# mainboard_motor_v1_0.net
KiCad netlist of a schematic drawn in Altium Designer
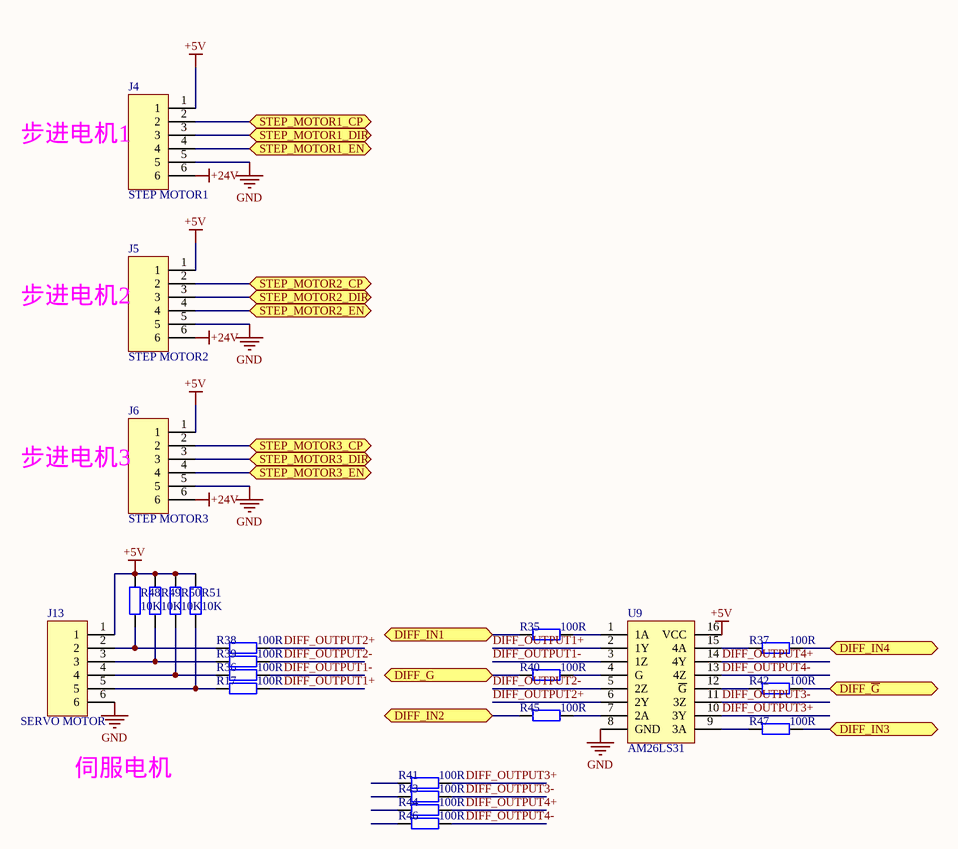
[diagram p0: mainboard_motor.v1.0.SchDoc]

(export (version "E")
  (design (tool "Eeschema 10.0.6"))
  (components
    (comp (ref "J4")
      (value "STEP MOTOR1")
      (footprint "XH2.54-6T")
      (libsource (lib "Connector") (part "SH-6"))
    )
    (comp (ref "J5")
      (value "STEP MOTOR2")
      (footprint "XH2.54-6T")
      (libsource (lib "Connector") (part "SH-6"))
    )
    (comp (ref "J6")
      (value "STEP MOTOR3")
      (footprint "XH2.54-6T")
      (libsource (lib "Connector") (part "SH-6"))
    )
    (comp (ref "J13")
      (value "SERVO MOTOR")
      (footprint "XH2.54-6T")
      (libsource (lib "Connector") (part "SH-6"))
    )
    (comp (ref "R17")
      (value "100R")
      (footprint "0805")
      (description "Resistor")
      (fields (field (name "PUBLISHER") "Altium Limited"))
      (libsource (lib "") (part "Res2_1"))
    )
    (comp (ref "R35")
      (value "100R")
      (footprint "0805")
      (description "Resistor")
      (fields (field (name "PUBLISHER") "Altium Limited"))
      (libsource (lib "") (part "Res2_1"))
    )
    (comp (ref "R36")
      (value "100R")
      (footprint "0805")
      (description "Resistor")
      (fields (field (name "PUBLISHER") "Altium Limited"))
      (libsource (lib "") (part "Res2_1"))
    )
    (comp (ref "R37")
      (value "100R")
      (footprint "0805")
      (description "Resistor")
      (fields (field (name "PUBLISHER") "Altium Limited"))
      (libsource (lib "") (part "Res2_1"))
    )
    (comp (ref "R38")
      (value "100R")
      (footprint "0805")
      (description "Resistor")
      (fields (field (name "PUBLISHER") "Altium Limited"))
      (libsource (lib "") (part "Res2_1"))
    )
    (comp (ref "R39")
      (value "100R")
      (footprint "0805")
      (description "Resistor")
      (fields (field (name "PUBLISHER") "Altium Limited"))
      (libsource (lib "") (part "Res2_1"))
    )
    (comp (ref "R40")
      (value "100R")
      (footprint "0805")
      (description "Resistor")
      (fields (field (name "PUBLISHER") "Altium Limited"))
      (libsource (lib "") (part "Res2_1"))
    )
    (comp (ref "R41")
      (value "100R")
      (footprint "0805")
      (description "Resistor")
      (fields (field (name "PUBLISHER") "Altium Limited"))
      (libsource (lib "") (part "Res2_1"))
    )
    (comp (ref "R42")
      (value "100R")
      (footprint "0805")
      (description "Resistor")
      (fields (field (name "PUBLISHER") "Altium Limited"))
      (libsource (lib "") (part "Res2_1"))
    )
    (comp (ref "R43")
      (value "100R")
      (footprint "0805")
      (description "Resistor")
      (fields (field (name "PUBLISHER") "Altium Limited"))
      (libsource (lib "") (part "Res2_1"))
    )
    (comp (ref "R44")
      (value "100R")
      (footprint "0805")
      (description "Resistor")
      (fields (field (name "PUBLISHER") "Altium Limited"))
      (libsource (lib "") (part "Res2_1"))
    )
    (comp (ref "R45")
      (value "100R")
      (footprint "0805")
      (description "Resistor")
      (fields (field (name "PUBLISHER") "Altium Limited"))
      (libsource (lib "") (part "Res2_1"))
    )
    (comp (ref "R46")
      (value "100R")
      (footprint "0805")
      (description "Resistor")
      (fields (field (name "PUBLISHER") "Altium Limited"))
      (libsource (lib "") (part "Res2_1"))
    )
    (comp (ref "R47")
      (value "100R")
      (footprint "0805")
      (description "Resistor")
      (fields (field (name "PUBLISHER") "Altium Limited"))
      (libsource (lib "") (part "Res2_1"))
    )
    (comp (ref "R48")
      (value "10K")
      (footprint "0805")
      (description "Resistor")
      (fields (field (name "PUBLISHER") "Altium Limited"))
      (libsource (lib "TIAN's Schlib") (part "Res2"))
    )
    (comp (ref "R49")
      (value "10K")
      (footprint "0805")
      (description "Resistor")
      (fields (field (name "PUBLISHER") "Altium Limited"))
      (libsource (lib "TIAN's Schlib") (part "Res2"))
    )
    (comp (ref "R50")
      (value "10K")
      (footprint "0805")
      (description "Resistor")
      (fields (field (name "PUBLISHER") "Altium Limited"))
      (libsource (lib "TIAN's Schlib") (part "Res2"))
    )
    (comp (ref "R51")
      (value "10K")
      (footprint "0805")
      (description "Resistor")
      (fields (field (name "PUBLISHER") "Altium Limited"))
      (libsource (lib "TIAN's Schlib") (part "Res2"))
    )
    (comp (ref "U9") (value "AM26LS31") (footprint "SO-16") (libsource (lib "Chip") (part "AM26LS31")))
  )
  (nets
    (net (code "1") (name "+5V") (class "Default")
      (node (ref "J13") (pin "1") (pinfunction "1_1") (pintype "passive"))
      (node (ref "J4") (pin "1") (pinfunction "1_1") (pintype "passive"))
      (node (ref "J5") (pin "1") (pinfunction "1_1") (pintype "passive"))
      (node (ref "J6") (pin "1") (pinfunction "1_1") (pintype "passive"))
      (node (ref "R48") (pin "1") (pinfunction "1_1") (pintype "passive"))
      (node (ref "R49") (pin "1") (pinfunction "1_1") (pintype "passive"))
      (node (ref "R50") (pin "1") (pinfunction "1_1") (pintype "passive"))
      (node (ref "R51") (pin "1") (pinfunction "1_1") (pintype "passive"))
      (node (ref "U9") (pin "16") (pinfunction "VCC_16") (pintype "passive"))
    )
    (net (code "2") (name "+24V") (class "Default")
      (node (ref "J4") (pin "6") (pinfunction "6_6") (pintype "passive"))
      (node (ref "J5") (pin "6") (pinfunction "6_6") (pintype "passive"))
      (node (ref "J6") (pin "6") (pinfunction "6_6") (pintype "passive"))
    )
    (net (code "3") (name "/DIFF_G") (class "Default")
      (node (ref "R40") (pin "2") (pinfunction "2_2") (pintype "passive"))
    )
    (net (code "4") (name "/DIFF_IN1") (class "Default")
      (node (ref "R35") (pin "2") (pinfunction "2_2") (pintype "passive"))
    )
    (net (code "5") (name "/DIFF_IN2") (class "Default")
      (node (ref "R45") (pin "2") (pinfunction "2_2") (pintype "passive"))
    )
    (net (code "6") (name "/DIFF_IN3") (class "Default")
      (node (ref "R47") (pin "1") (pinfunction "1_1") (pintype "passive"))
    )
    (net (code "7") (name "/DIFF_IN4") (class "Default")
      (node (ref "R37") (pin "1") (pinfunction "1_1") (pintype "passive"))
    )
    (net (code "8") (name "/DIFF_OUTPUT1+") (class "Default")
      (node (ref "R17") (pin "1") (pinfunction "1_1") (pintype "passive"))
      (node (ref "U9") (pin "2") (pinfunction "1Y_2") (pintype "passive"))
    )
    (net (code "9") (name "/DIFF_OUTPUT1-") (class "Default")
      (node (ref "R36") (pin "1") (pinfunction "1_1") (pintype "passive"))
      (node (ref "U9") (pin "3") (pinfunction "1Z_3") (pintype "passive"))
    )
    (net (code "10") (name "/DIFF_OUTPUT2+") (class "Default")
      (node (ref "R38") (pin "1") (pinfunction "1_1") (pintype "passive"))
      (node (ref "U9") (pin "6") (pinfunction "2Y_6") (pintype "passive"))
    )
    (net (code "11") (name "/DIFF_OUTPUT2-") (class "Default")
      (node (ref "R39") (pin "1") (pinfunction "1_1") (pintype "passive"))
      (node (ref "U9") (pin "5") (pinfunction "2Z_5") (pintype "passive"))
    )
    (net (code "12") (name "/DIFF_OUTPUT3+") (class "Default")
      (node (ref "R41") (pin "1") (pinfunction "1_1") (pintype "passive"))
      (node (ref "U9") (pin "10") (pinfunction "3Y_10") (pintype "passive"))
    )
    (net (code "13") (name "/DIFF_OUTPUT3-") (class "Default")
      (node (ref "R43") (pin "1") (pinfunction "1_1") (pintype "passive"))
      (node (ref "U9") (pin "11") (pinfunction "3Z_11") (pintype "passive"))
    )
    (net (code "14") (name "/DIFF_OUTPUT4+") (class "Default")
      (node (ref "R44") (pin "1") (pinfunction "1_1") (pintype "passive"))
      (node (ref "U9") (pin "14") (pinfunction "4Y_14") (pintype "passive"))
    )
    (net (code "15") (name "/DIFF_OUTPUT4-") (class "Default")
      (node (ref "R46") (pin "1") (pinfunction "1_1") (pintype "passive"))
      (node (ref "U9") (pin "13") (pinfunction "4Z_13") (pintype "passive"))
    )
    (net (code "16") (name "/DIFF_~{G}") (class "Default")
      (node (ref "R42") (pin "1") (pinfunction "1_1") (pintype "passive"))
    )
    (net (code "17") (name "/STEP_MOTOR1_CP") (class "Default")
      (node (ref "J4") (pin "2") (pinfunction "2_2") (pintype "passive"))
    )
    (net (code "18") (name "/STEP_MOTOR1_DIR") (class "Default")
      (node (ref "J4") (pin "3") (pinfunction "3_3") (pintype "passive"))
    )
    (net (code "19") (name "/STEP_MOTOR1_EN") (class "Default")
      (node (ref "J4") (pin "4") (pinfunction "4_4") (pintype "passive"))
    )
    (net (code "20") (name "/STEP_MOTOR2_CP") (class "Default")
      (node (ref "J5") (pin "2") (pinfunction "2_2") (pintype "passive"))
    )
    (net (code "21") (name "/STEP_MOTOR2_DIR") (class "Default")
      (node (ref "J5") (pin "3") (pinfunction "3_3") (pintype "passive"))
    )
    (net (code "22") (name "/STEP_MOTOR2_EN") (class "Default")
      (node (ref "J5") (pin "4") (pinfunction "4_4") (pintype "passive"))
    )
    (net (code "23") (name "/STEP_MOTOR3_CP") (class "Default")
      (node (ref "J6") (pin "2") (pinfunction "2_2") (pintype "passive"))
    )
    (net (code "24") (name "/STEP_MOTOR3_DIR") (class "Default")
      (node (ref "J6") (pin "3") (pinfunction "3_3") (pintype "passive"))
    )
    (net (code "25") (name "/STEP_MOTOR3_EN") (class "Default")
      (node (ref "J6") (pin "4") (pinfunction "4_4") (pintype "passive"))
    )
    (net (code "26") (name "GND") (class "Default")
      (node (ref "J13") (pin "6") (pinfunction "6_6") (pintype "passive"))
      (node (ref "J4") (pin "5") (pinfunction "5_5") (pintype "passive"))
      (node (ref "J5") (pin "5") (pinfunction "5_5") (pintype "passive"))
      (node (ref "J6") (pin "5") (pinfunction "5_5") (pintype "passive"))
      (node (ref "U9") (pin "8") (pinfunction "GND_8") (pintype "passive"))
    )
    (net (code "27") (name "Net-(J13-Pad2)") (class "Default")
      (node (ref "J13") (pin "2") (pinfunction "2_2") (pintype "passive"))
      (node (ref "R38") (pin "2") (pinfunction "2_2") (pintype "passive"))
      (node (ref "R48") (pin "2") (pinfunction "2_2") (pintype "passive"))
    )
    (net (code "28") (name "Net-(J13-Pad3)") (class "Default")
      (node (ref "J13") (pin "3") (pinfunction "3_3") (pintype "passive"))
      (node (ref "R39") (pin "2") (pinfunction "2_2") (pintype "passive"))
      (node (ref "R49") (pin "2") (pinfunction "2_2") (pintype "passive"))
    )
    (net (code "29") (name "Net-(J13-Pad4)") (class "Default")
      (node (ref "J13") (pin "4") (pinfunction "4_4") (pintype "passive"))
      (node (ref "R36") (pin "2") (pinfunction "2_2") (pintype "passive"))
      (node (ref "R50") (pin "2") (pinfunction "2_2") (pintype "passive"))
    )
    (net (code "30") (name "Net-(J13-Pad5)") (class "Default")
      (node (ref "J13") (pin "5") (pinfunction "5_5") (pintype "passive"))
      (node (ref "R17") (pin "2") (pinfunction "2_2") (pintype "passive"))
      (node (ref "R51") (pin "2") (pinfunction "2_2") (pintype "passive"))
    )
    (net (code "31") (name "Net-(U9-1A)") (class "Default")
      (node (ref "R35") (pin "1") (pinfunction "1_1") (pintype "passive"))
      (node (ref "U9") (pin "1") (pinfunction "1A_1") (pintype "passive"))
    )
    (net (code "32") (name "Net-(U9-2A)") (class "Default")
      (node (ref "R45") (pin "1") (pinfunction "1_1") (pintype "passive"))
      (node (ref "U9") (pin "7") (pinfunction "2A_7") (pintype "passive"))
    )
    (net (code "33") (name "Net-(U9-3A)") (class "Default")
      (node (ref "R47") (pin "2") (pinfunction "2_2") (pintype "passive"))
      (node (ref "U9") (pin "9") (pinfunction "3A_9") (pintype "passive"))
    )
    (net (code "34") (name "Net-(U9-4A)") (class "Default")
      (node (ref "R37") (pin "2") (pinfunction "2_2") (pintype "passive"))
      (node (ref "U9") (pin "15") (pinfunction "4A_15") (pintype "passive"))
    )
    (net (code "35") (name "Net-(U9-G)") (class "Default")
      (node (ref "R40") (pin "1") (pinfunction "1_1") (pintype "passive"))
      (node (ref "U9") (pin "4") (pinfunction "G_4") (pintype "passive"))
    )
    (net (code "36") (name "Net-(U9-~{G})") (class "Default")
      (node (ref "R42") (pin "2") (pinfunction "2_2") (pintype "passive"))
      (node (ref "U9") (pin "12") (pinfunction "~{G}_12") (pintype "passive"))
    )
    (net (code "37") (name "unconnected-(R41-Pad2)") (class "Default")
      (node (ref "R41") (pin "2") (pinfunction "2_2") (pintype "passive"))
    )
    (net (code "38") (name "unconnected-(R43-Pad2)") (class "Default")
      (node (ref "R43") (pin "2") (pinfunction "2_2") (pintype "passive"))
    )
    (net (code "39") (name "unconnected-(R44-Pad2)") (class "Default")
      (node (ref "R44") (pin "2") (pinfunction "2_2") (pintype "passive"))
    )
    (net (code "40") (name "unconnected-(R46-Pad2)") (class "Default")
      (node (ref "R46") (pin "2") (pinfunction "2_2") (pintype "passive"))
    )
  )
)
